# VC8Erework.net
KiCad netlist of a schematic drawn in EAGLE
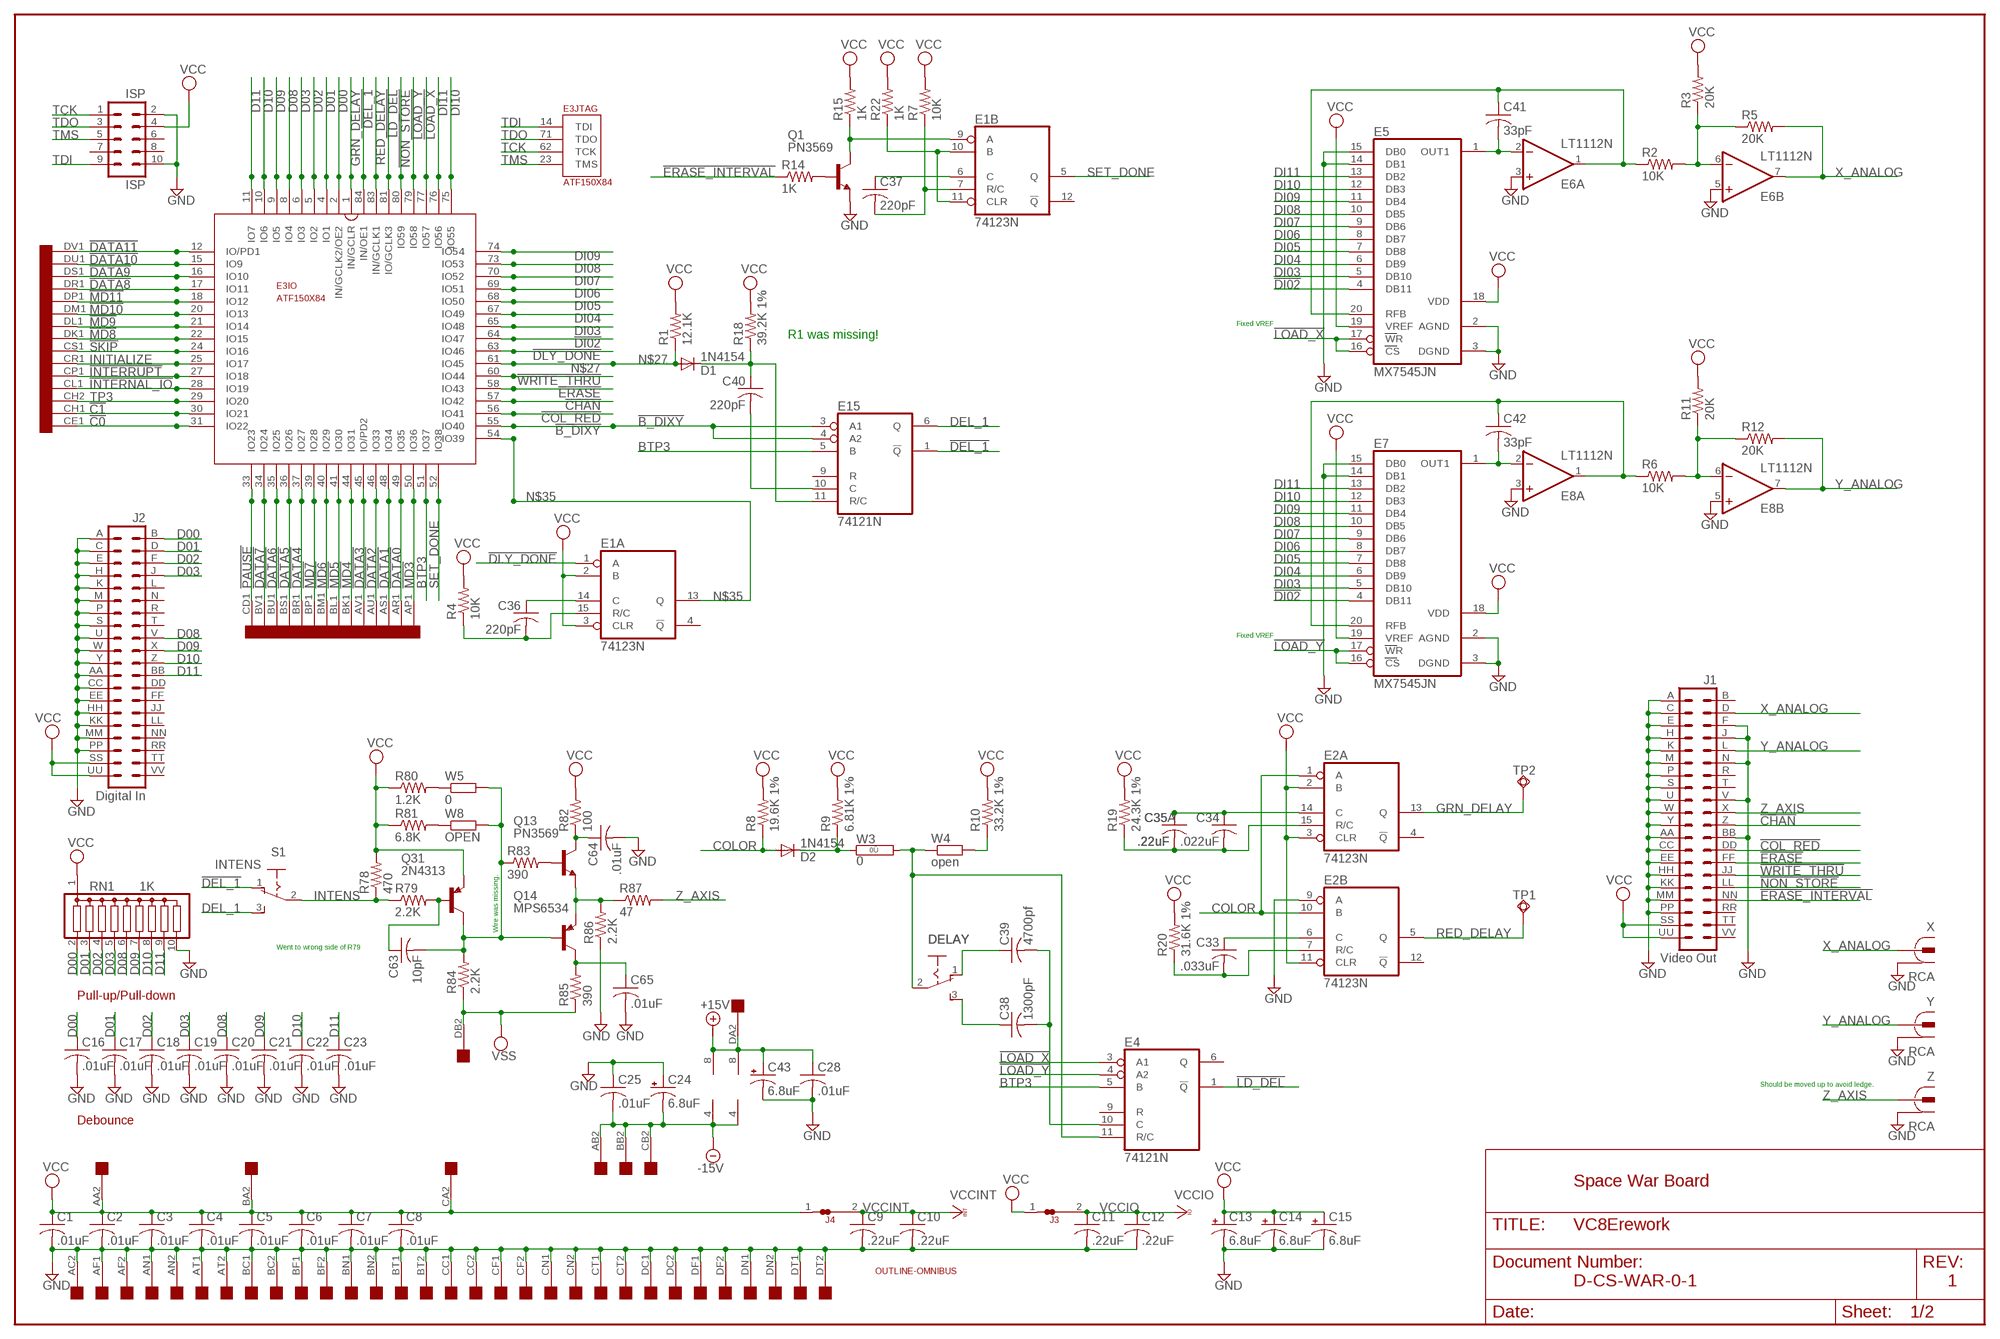
[diagram p0: schematic, sheet 1]

(export (version "E")
  (design (tool "Eeschema 10.0.6"))
  (components
    (comp (ref "C1")
      (value ".01uF")
      (footprint "eagle-import:C063-025X075")
      (libsource (lib "eagle-import") (part "C-US"))
    )
    (comp (ref "C2")
      (value ".01uF")
      (footprint "eagle-import:C063-025X075")
      (libsource (lib "eagle-import") (part "C-US"))
    )
    (comp (ref "C3")
      (value ".01uF")
      (footprint "eagle-import:C063-025X075")
      (libsource (lib "eagle-import") (part "C-US"))
    )
    (comp (ref "C4")
      (value ".01uF")
      (footprint "eagle-import:C063-025X075")
      (libsource (lib "eagle-import") (part "C-US"))
    )
    (comp (ref "C5")
      (value ".01uF")
      (footprint "eagle-import:C063-025X075")
      (libsource (lib "eagle-import") (part "C-US"))
    )
    (comp (ref "C6")
      (value ".01uF")
      (footprint "eagle-import:C063-025X075")
      (libsource (lib "eagle-import") (part "C-US"))
    )
    (comp (ref "C7")
      (value ".01uF")
      (footprint "eagle-import:C063-025X075")
      (libsource (lib "eagle-import") (part "C-US"))
    )
    (comp (ref "C8")
      (value ".01uF")
      (footprint "eagle-import:C063-025X075")
      (libsource (lib "eagle-import") (part "C-US"))
    )
    (comp (ref "C9")
      (value ".22uF")
      (footprint "eagle-import:C063-025X075")
      (libsource (lib "eagle-import") (part "C-US"))
    )
    (comp (ref "C10")
      (value ".22uF")
      (footprint "eagle-import:C063-025X075")
      (libsource (lib "eagle-import") (part "C-US"))
    )
    (comp (ref "C11")
      (value ".22uF")
      (footprint "eagle-import:C063-025X075")
      (libsource (lib "eagle-import") (part "C-US"))
    )
    (comp (ref "C12")
      (value ".22uF")
      (footprint "eagle-import:C063-025X075")
      (libsource (lib "eagle-import") (part "C-US"))
    )
    (comp (ref "C13")
      (value "6.8uF")
      (footprint "eagle-import:E12-8")
      (libsource (lib "eagle-import") (part "CPOL-USE20-8AXIAL"))
    )
    (comp (ref "C14")
      (value "6.8uF")
      (footprint "eagle-import:E12-8")
      (libsource (lib "eagle-import") (part "CPOL-USE20-8AXIAL"))
    )
    (comp (ref "C15")
      (value "6.8uF")
      (footprint "eagle-import:E12-8")
      (libsource (lib "eagle-import") (part "CPOL-USE20-8AXIAL"))
    )
    (comp (ref "C16")
      (value ".01uF")
      (footprint "eagle-import:C063-025X075")
      (libsource (lib "eagle-import") (part "C-US"))
    )
    (comp (ref "C17")
      (value ".01uF")
      (footprint "eagle-import:C063-025X075")
      (libsource (lib "eagle-import") (part "C-US"))
    )
    (comp (ref "C18")
      (value ".01uF")
      (footprint "eagle-import:C063-025X075")
      (libsource (lib "eagle-import") (part "C-US"))
    )
    (comp (ref "C19")
      (value ".01uF")
      (footprint "eagle-import:C063-025X075")
      (libsource (lib "eagle-import") (part "C-US"))
    )
    (comp (ref "C20")
      (value ".01uF")
      (footprint "eagle-import:C063-025X075")
      (libsource (lib "eagle-import") (part "C-US"))
    )
    (comp (ref "C21")
      (value ".01uF")
      (footprint "eagle-import:C063-025X075")
      (libsource (lib "eagle-import") (part "C-US"))
    )
    (comp (ref "C22")
      (value ".01uF")
      (footprint "eagle-import:C063-025X075")
      (libsource (lib "eagle-import") (part "C-US"))
    )
    (comp (ref "C23")
      (value ".01uF")
      (footprint "eagle-import:C063-025X075")
      (libsource (lib "eagle-import") (part "C-US"))
    )
    (comp (ref "C24")
      (value "6.8uF")
      (footprint "eagle-import:E12-8")
      (libsource (lib "eagle-import") (part "CPOL-USE20-8AXIAL"))
    )
    (comp (ref "C25")
      (value ".01uF")
      (footprint "eagle-import:C063-025X075")
      (libsource (lib "eagle-import") (part "C-US"))
    )
    (comp (ref "C28")
      (value ".01uF")
      (footprint "eagle-import:C063-025X075")
      (libsource (lib "eagle-import") (part "C-US"))
    )
    (comp (ref "C33")
      (value ".033uF")
      (footprint "eagle-import:C102-043X133")
      (libsource (lib "eagle-import") (part "C-US102-043X133"))
    )
    (comp (ref "C34")
      (value ".022uF")
      (footprint "eagle-import:C102-043X133")
      (libsource (lib "eagle-import") (part "C-US102-043X133"))
    )
    (comp (ref "C35")
      (value ".22uF")
      (footprint "eagle-import:C050-025X075")
      (libsource (lib "eagle-import") (part "C-US050-025X075"))
    )
    (comp (ref "C35A")
      (value ".22uF")
      (footprint "eagle-import:C102-043X133")
      (libsource (lib "eagle-import") (part "C-US102-043X133"))
    )
    (comp (ref "C36")
      (value "220pF")
      (footprint "eagle-import:C063-025X075")
      (libsource (lib "eagle-import") (part "C-US"))
    )
    (comp (ref "C37")
      (value "220pF")
      (footprint "eagle-import:C063-025X075")
      (libsource (lib "eagle-import") (part "C-US"))
    )
    (comp (ref "C38")
      (value "1300pF")
      (footprint "eagle-import:C150-054X183")
      (libsource (lib "eagle-import") (part "C-US150-054X183"))
    )
    (comp (ref "C39")
      (value "4700pf")
      (footprint "eagle-import:C102-043X133")
      (libsource (lib "eagle-import") (part "C-US102-043X133"))
    )
    (comp (ref "C40")
      (value "220pF")
      (footprint "eagle-import:C063-025X075")
      (libsource (lib "eagle-import") (part "C-US"))
    )
    (comp (ref "C41")
      (value "33pF")
      (footprint "eagle-import:C063-025X075")
      (libsource (lib "eagle-import") (part "C-US"))
    )
    (comp (ref "C42")
      (value "33pF")
      (footprint "eagle-import:C063-025X075")
      (libsource (lib "eagle-import") (part "C-US"))
    )
    (comp (ref "C43")
      (value "6.8uF")
      (footprint "eagle-import:E12-8")
      (libsource (lib "eagle-import") (part "CPOL-USE20-8AXIAL"))
    )
    (comp (ref "C63")
      (value "10pF")
      (footprint "eagle-import:C063-025X075")
      (libsource (lib "eagle-import") (part "C-US"))
    )
    (comp (ref "C64")
      (value ".01uF")
      (footprint "eagle-import:C063-025X075")
      (libsource (lib "eagle-import") (part "C-US"))
    )
    (comp (ref "C65")
      (value ".01uF")
      (footprint "eagle-import:C063-025X075")
      (libsource (lib "eagle-import") (part "C-US"))
    )
    (comp (ref "D1")
      (value "1N4154")
      (footprint "eagle-import:DO35-10")
      (libsource (lib "eagle-import") (part "DIODE-DO35-10"))
    )
    (comp (ref "D2")
      (value "1N4154")
      (footprint "eagle-import:DO35-10")
      (libsource (lib "eagle-import") (part "DIODE-DO35-10"))
    )
    (comp (ref "DELAY")
      (value "DELAY")
      (footprint "eagle-import:M251")
      (libsource (lib "eagle-import") (part "M251"))
    )
    (comp (ref "E1")
      (value "74123N")
      (footprint "eagle-import:DIL16")
      (libsource (lib "eagle-import") (part "74123N"))
    )
    (comp (ref "E2")
      (value "74123N")
      (footprint "eagle-import:DIL16")
      (libsource (lib "eagle-import") (part "74123N"))
    )
    (comp (ref "E3")
      (value "ATF150X84")
      (footprint "eagle-import:S84")
      (libsource (lib "eagle-import") (part "ATF150X84"))
    )
    (comp (ref "E4")
      (value "74121N")
      (footprint "eagle-import:DIL14")
      (libsource (lib "eagle-import") (part "74121N"))
    )
    (comp (ref "E5")
      (value "MX7545JN")
      (footprint "eagle-import:DIL20")
      (fields (field (name "MPN") "MX7545JN+"))
      (libsource (lib "eagle-import") (part "MX7545JN"))
    )
    (comp (ref "E6")
      (value "LT1112N")
      (footprint "eagle-import:DIL08")
      (libsource (lib "eagle-import") (part "1458NLM"))
    )
    (comp (ref "E7")
      (value "MX7545JN")
      (footprint "eagle-import:DIL20")
      (fields (field (name "MPN") "MX7545JN+"))
      (libsource (lib "eagle-import") (part "MX7545JN"))
    )
    (comp (ref "E8")
      (value "LT1112N")
      (footprint "eagle-import:DIL08")
      (libsource (lib "eagle-import") (part "1458NLM"))
    )
    (comp (ref "E15")
      (value "74121N")
      (footprint "eagle-import:DIL14")
      (libsource (lib "eagle-import") (part "74121N"))
    )
    (comp (ref "ISP")
      (value "ISP")
      (footprint "eagle-import:ML10")
      (libsource (lib "eagle-import") (part "ML10"))
    )
    (comp (ref "J1")
      (value "Video Out")
      (footprint "eagle-import:DEC40PINH")
      (libsource (lib "eagle-import") (part "DEC40PINH"))
    )
    (comp (ref "J2")
      (value "Digital In")
      (footprint "eagle-import:DEC40PINH")
      (libsource (lib "eagle-import") (part "DEC40PINH"))
    )
    (comp (ref "J3")
      (value "JUMPER-NC1")
      (footprint "eagle-import:NC1")
      (libsource (lib "eagle-import") (part "JUMPER-NC1"))
    )
    (comp (ref "J4")
      (value "JUMPER-NC1")
      (footprint "eagle-import:NC1")
      (libsource (lib "eagle-import") (part "JUMPER-NC1"))
    )
    (comp (ref "OMNIBUS")
      (value "QUAD")
      (footprint "eagle-import:EDGE-CON8")
      (libsource (lib "eagle-import") (part "QUAD"))
    )
    (comp (ref "Q1")
      (value "PN3569")
      (footprint "eagle-import:TO18-")
      (libsource (lib "eagle-import") (part "-NPN-TO18-"))
    )
    (comp (ref "Q13")
      (value "PN3569")
      (footprint "eagle-import:TO5")
      (libsource (lib "eagle-import") (part "-NPN-TO5"))
    )
    (comp (ref "Q14")
      (value "MPS6534")
      (footprint "eagle-import:TO5")
      (libsource (lib "eagle-import") (part "-PNP-TO5"))
    )
    (comp (ref "Q31")
      (value "2N4313")
      (footprint "eagle-import:TO5")
      (libsource (lib "eagle-import") (part "-PNP-TO5"))
    )
    (comp (ref "R1")
      (value "12.1K")
      (footprint "eagle-import:0207_7")
      (libsource (lib "eagle-import") (part "R-US_0207/7"))
    )
    (comp (ref "R2")
      (value "10K")
      (footprint "eagle-import:0207_10")
      (libsource (lib "eagle-import") (part "R-US_0207/10"))
    )
    (comp (ref "R3")
      (value "20K")
      (footprint "eagle-import:0207_10")
      (libsource (lib "eagle-import") (part "R-US_0207/10"))
    )
    (comp (ref "R4")
      (value "10K")
      (footprint "eagle-import:0207_10")
      (libsource (lib "eagle-import") (part "R-US_0207/10"))
    )
    (comp (ref "R5")
      (value "20K")
      (footprint "eagle-import:0207_10")
      (libsource (lib "eagle-import") (part "R-US_0207/10"))
    )
    (comp (ref "R6")
      (value "10K")
      (footprint "eagle-import:0207_10")
      (libsource (lib "eagle-import") (part "R-US_0207/10"))
    )
    (comp (ref "R7")
      (value "10K")
      (footprint "eagle-import:0207_10")
      (libsource (lib "eagle-import") (part "R-US_0207/10"))
    )
    (comp (ref "R8")
      (value "19.6K 1%")
      (footprint "eagle-import:0207_15")
      (libsource (lib "eagle-import") (part "R-US_0207/15"))
    )
    (comp (ref "R9")
      (value "6.81K 1%")
      (footprint "eagle-import:0207_15")
      (libsource (lib "eagle-import") (part "R-US_0207/15"))
    )
    (comp (ref "R10")
      (value "33.2K 1%")
      (footprint "eagle-import:0207_15")
      (libsource (lib "eagle-import") (part "R-US_0207/15"))
    )
    (comp (ref "R11")
      (value "20K")
      (footprint "eagle-import:0207_10")
      (libsource (lib "eagle-import") (part "R-US_0207/10"))
    )
    (comp (ref "R12")
      (value "20K")
      (footprint "eagle-import:0207_10")
      (libsource (lib "eagle-import") (part "R-US_0207/10"))
    )
    (comp (ref "R14")
      (value "1K")
      (footprint "eagle-import:0207_10")
      (libsource (lib "eagle-import") (part "R-US_0207/10"))
    )
    (comp (ref "R15")
      (value "1K")
      (footprint "eagle-import:0207_10")
      (libsource (lib "eagle-import") (part "R-US_0207/10"))
    )
    (comp (ref "R18")
      (value "39.2K 1%")
      (footprint "eagle-import:0207_15")
      (libsource (lib "eagle-import") (part "R-US_0207/15"))
    )
    (comp (ref "R19")
      (value "24.3K 1%")
      (footprint "eagle-import:0207_15")
      (libsource (lib "eagle-import") (part "R-US_0207/15"))
    )
    (comp (ref "R20")
      (value "31.6K 1%")
      (footprint "eagle-import:0207_15")
      (libsource (lib "eagle-import") (part "R-US_0207/15"))
    )
    (comp (ref "R22")
      (value "1K")
      (footprint "eagle-import:0207_10")
      (libsource (lib "eagle-import") (part "R-US_0207/10"))
    )
    (comp (ref "R78")
      (value "470")
      (footprint "eagle-import:0207_10")
      (libsource (lib "eagle-import") (part "R-US_0207/10"))
    )
    (comp (ref "R79")
      (value "2.2K")
      (footprint "eagle-import:0207_10")
      (libsource (lib "eagle-import") (part "R-US_0207/10"))
    )
    (comp (ref "R80")
      (value "1.2K")
      (footprint "eagle-import:0207_10")
      (libsource (lib "eagle-import") (part "R-US_0207/10"))
    )
    (comp (ref "R81")
      (value "6.8K")
      (footprint "eagle-import:0207_10")
      (libsource (lib "eagle-import") (part "R-US_0207/10"))
    )
    (comp (ref "R82")
      (value "100")
      (footprint "eagle-import:0207_10")
      (libsource (lib "eagle-import") (part "R-US_0207/10"))
    )
    (comp (ref "R83")
      (value "390")
      (footprint "eagle-import:0207_10")
      (libsource (lib "eagle-import") (part "R-US_0207/10"))
    )
    (comp (ref "R84")
      (value "2.2K")
      (footprint "eagle-import:0207_10")
      (libsource (lib "eagle-import") (part "R-US_0207/10"))
    )
    (comp (ref "R85")
      (value "390")
      (footprint "eagle-import:0207_10")
      (libsource (lib "eagle-import") (part "R-US_0207/10"))
    )
    (comp (ref "R86")
      (value "2.2K")
      (footprint "eagle-import:0207_10")
      (libsource (lib "eagle-import") (part "R-US_0207/10"))
    )
    (comp (ref "R87")
      (value "47")
      (footprint "eagle-import:0207_10")
      (libsource (lib "eagle-import") (part "R-US_0207/10"))
    )
    (comp (ref "RN1")
      (value "1K")
      (footprint "eagle-import:SIL10")
      (libsource (lib "eagle-import") (part "G09R"))
    )
    (comp (ref "S1")
      (value "INTENS")
      (footprint "eagle-import:M251")
      (libsource (lib "eagle-import") (part "M251"))
    )
    (comp (ref "TP1")
      (value "TPSQPAD1-17")
      (footprint "eagle-import:P1-17")
      (libsource (lib "eagle-import") (part "TPSQPAD1-17"))
    )
    (comp (ref "TP2")
      (value "TPSQPAD1-17")
      (footprint "eagle-import:P1-17")
      (libsource (lib "eagle-import") (part "TPSQPAD1-17"))
    )
    (comp (ref "U$1")
      (value "OUTLINE-OMNIBUS")
      (footprint "eagle-import:OMNIBUS")
      (libsource (lib "eagle-import") (part "OUTLINE-OMNIBUS"))
    )
    (comp (ref "W3")
      (value "0")
      (footprint "eagle-import:0R_10")
      (libsource (lib "eagle-import") (part "0R"))
    )
    (comp (ref "W4")
      (value "open")
      (footprint "eagle-import:0207_10")
      (libsource (lib "eagle-import") (part "R-EU_0207/10"))
    )
    (comp (ref "W5")
      (value "0")
      (footprint "eagle-import:0207_10")
      (libsource (lib "eagle-import") (part "R-EU_0207/10"))
    )
    (comp (ref "W8")
      (value "OPEN")
      (footprint "eagle-import:0207_10")
      (libsource (lib "eagle-import") (part "R-EU_0207/10"))
    )
    (comp (ref "X")
      (value "RCA")
      (footprint "eagle-import:RCA")
      (libsource (lib "eagle-import") (part "RCA"))
    )
    (comp (ref "Y")
      (value "RCA")
      (footprint "eagle-import:RCA")
      (libsource (lib "eagle-import") (part "RCA"))
    )
    (comp (ref "Z")
      (value "RCA")
      (footprint "eagle-import:RCA")
      (libsource (lib "eagle-import") (part "RCA"))
    )
  )
  (nets
    (net (code "1") (name "+15V") (class "Default")
      (node (ref "C28") (pin "1") (pinfunction "1_1") (pintype "passive"))
      (node (ref "C43") (pin "+") (pinfunction "+_+") (pintype "passive"))
      (node (ref "E6") (pin "8") (pinfunction "V+_8") (pintype "power_in"))
      (node (ref "E8") (pin "8") (pinfunction "V+_8") (pintype "power_in"))
      (node (ref "OMNIBUS") (pin "DA2") (pinfunction "1_DA2") (pintype "bidirectional"))
    )
    (net (code "2") (name "-15V") (class "Default")
      (node (ref "C24") (pin "-") (pinfunction "-_-") (pintype "passive"))
      (node (ref "C25") (pin "2") (pinfunction "2_2") (pintype "passive"))
      (node (ref "E6") (pin "4") (pinfunction "V-_4") (pintype "power_in"))
      (node (ref "E8") (pin "4") (pinfunction "V-_4") (pintype "power_in"))
      (node (ref "OMNIBUS") (pin "AB2") (pinfunction "1_AB2") (pintype "bidirectional"))
      (node (ref "OMNIBUS") (pin "BB2") (pinfunction "1_BB2") (pintype "bidirectional"))
      (node (ref "OMNIBUS") (pin "CB2") (pinfunction "1_CB2") (pintype "bidirectional"))
    )
    (net (code "3") (name "BTP3") (class "Default")
      (node (ref "E15") (pin "5") (pinfunction "B_5") (pintype "input"))
      (node (ref "E3") (pin "51") (pinfunction "IO37_51") (pintype "bidirectional"))
      (node (ref "E4") (pin "5") (pinfunction "B_5") (pintype "input"))
    )
    (net (code "4") (name "COLOR") (class "Default")
      (node (ref "D2") (pin "A") (pinfunction "A_A") (pintype "passive"))
      (node (ref "E2") (pin "1") (pinfunction "A_1") (pintype "input"))
      (node (ref "E2") (pin "10") (pinfunction "B_10") (pintype "input"))
      (node (ref "R8") (pin "1") (pinfunction "1_1") (pintype "passive"))
    )
    (net (code "5") (name "D00") (class "Default")
      (node (ref "C16") (pin "1") (pinfunction "1_1") (pintype "passive"))
      (node (ref "E3") (pin "2") (pinfunction "IN/GCLK2/OE2_2") (pintype "input"))
      (node (ref "J2") (pin "B") (pinfunction "2_B") (pintype "bidirectional"))
      (node (ref "RN1") (pin "2") (pinfunction "2_2") (pintype "passive"))
    )
    (net (code "6") (name "D01") (class "Default")
      (node (ref "C17") (pin "1") (pinfunction "1_1") (pintype "passive"))
      (node (ref "E3") (pin "4") (pinfunction "IO1_4") (pintype "bidirectional"))
      (node (ref "J2") (pin "D") (pinfunction "4_D") (pintype "bidirectional"))
      (node (ref "RN1") (pin "3") (pinfunction "3_3") (pintype "passive"))
    )
    (net (code "7") (name "D02") (class "Default")
      (node (ref "C18") (pin "1") (pinfunction "1_1") (pintype "passive"))
      (node (ref "E3") (pin "5") (pinfunction "IO2_5") (pintype "bidirectional"))
      (node (ref "J2") (pin "F") (pinfunction "6_F") (pintype "bidirectional"))
      (node (ref "RN1") (pin "4") (pinfunction "4_4") (pintype "passive"))
    )
    (net (code "8") (name "D03") (class "Default")
      (node (ref "C19") (pin "1") (pinfunction "1_1") (pintype "passive"))
      (node (ref "E3") (pin "6") (pinfunction "IO3_6") (pintype "bidirectional"))
      (node (ref "J2") (pin "J") (pinfunction "8_J") (pintype "bidirectional"))
      (node (ref "RN1") (pin "5") (pinfunction "5_5") (pintype "passive"))
    )
    (net (code "9") (name "D08") (class "Default")
      (node (ref "C20") (pin "1") (pinfunction "1_1") (pintype "passive"))
      (node (ref "E3") (pin "8") (pinfunction "IO4_8") (pintype "bidirectional"))
      (node (ref "J2") (pin "V") (pinfunction "18_V") (pintype "bidirectional"))
      (node (ref "RN1") (pin "6") (pinfunction "6_6") (pintype "passive"))
    )
    (net (code "10") (name "D09") (class "Default")
      (node (ref "C21") (pin "1") (pinfunction "1_1") (pintype "passive"))
      (node (ref "E3") (pin "9") (pinfunction "IO5_9") (pintype "bidirectional"))
      (node (ref "J2") (pin "X") (pinfunction "20_X") (pintype "bidirectional"))
      (node (ref "RN1") (pin "7") (pinfunction "7_7") (pintype "passive"))
    )
    (net (code "11") (name "D10") (class "Default")
      (node (ref "C22") (pin "1") (pinfunction "1_1") (pintype "passive"))
      (node (ref "E3") (pin "10") (pinfunction "IO6_10") (pintype "bidirectional"))
      (node (ref "J2") (pin "Z") (pinfunction "22_Z") (pintype "bidirectional"))
      (node (ref "RN1") (pin "8") (pinfunction "8_8") (pintype "passive"))
    )
    (net (code "12") (name "D11") (class "Default")
      (node (ref "C23") (pin "1") (pinfunction "1_1") (pintype "passive"))
      (node (ref "E3") (pin "11") (pinfunction "IO7_11") (pintype "bidirectional"))
      (node (ref "J2") (pin "BB") (pinfunction "24_BB") (pintype "bidirectional"))
      (node (ref "RN1") (pin "9") (pinfunction "9_9") (pintype "passive"))
    )
    (net (code "13") (name "DEL_1") (class "Default")
      (node (ref "E15") (pin "6") (pinfunction "Q_6") (pintype "output"))
      (node (ref "S1") (pin "3") (pinfunction "S_3") (pintype "passive"))
    )
    (net (code "14") (name "DI03") (class "Default")
      (node (ref "E3") (pin "65") (pinfunction "IO48_65") (pintype "bidirectional"))
      (node (ref "E5") (pin "5") (pinfunction "DB10_5") (pintype "input"))
      (node (ref "E7") (pin "5") (pinfunction "DB10_5") (pintype "input"))
    )
    (net (code "15") (name "DI04") (class "Default")
      (node (ref "E3") (pin "67") (pinfunction "IO49_67") (pintype "bidirectional"))
      (node (ref "E5") (pin "6") (pinfunction "DB9_6") (pintype "input"))
      (node (ref "E7") (pin "6") (pinfunction "DB9_6") (pintype "input"))
    )
    (net (code "16") (name "DI05") (class "Default")
      (node (ref "E3") (pin "68") (pinfunction "IO50_68") (pintype "bidirectional"))
      (node (ref "E5") (pin "7") (pinfunction "DB8_7") (pintype "input"))
      (node (ref "E7") (pin "7") (pinfunction "DB8_7") (pintype "input"))
    )
    (net (code "17") (name "DI06") (class "Default")
      (node (ref "E3") (pin "69") (pinfunction "IO51_69") (pintype "bidirectional"))
      (node (ref "E5") (pin "8") (pinfunction "DB7_8") (pintype "input"))
      (node (ref "E7") (pin "8") (pinfunction "DB7_8") (pintype "input"))
    )
    (net (code "18") (name "DI07") (class "Default")
      (node (ref "E3") (pin "70") (pinfunction "IO52_70") (pintype "bidirectional"))
      (node (ref "E5") (pin "9") (pinfunction "DB6_9") (pintype "input"))
      (node (ref "E7") (pin "9") (pinfunction "DB6_9") (pintype "input"))
    )
    (net (code "19") (name "DI08") (class "Default")
      (node (ref "E3") (pin "73") (pinfunction "IO53_73") (pintype "bidirectional"))
      (node (ref "E5") (pin "10") (pinfunction "DB5_10") (pintype "input"))
      (node (ref "E7") (pin "10") (pinfunction "DB5_10") (pintype "input"))
    )
    (net (code "20") (name "DI09") (class "Default")
      (node (ref "E3") (pin "74") (pinfunction "IO54_74") (pintype "bidirectional"))
      (node (ref "E5") (pin "11") (pinfunction "DB4_11") (pintype "input"))
      (node (ref "E7") (pin "11") (pinfunction "DB4_11") (pintype "input"))
    )
    (net (code "21") (name "DI10") (class "Default")
      (node (ref "E3") (pin "75") (pinfunction "IO55_75") (pintype "bidirectional"))
      (node (ref "E5") (pin "12") (pinfunction "DB3_12") (pintype "input"))
      (node (ref "E7") (pin "12") (pinfunction "DB3_12") (pintype "input"))
    )
    (net (code "22") (name "DI11") (class "Default")
      (node (ref "E3") (pin "76") (pinfunction "IO56_76") (pintype "bidirectional"))
      (node (ref "E5") (pin "13") (pinfunction "DB2_13") (pintype "input"))
      (node (ref "E7") (pin "13") (pinfunction "DB2_13") (pintype "input"))
    )
    (net (code "23") (name "GND") (class "Default")
      (node (ref "C1") (pin "2") (pinfunction "2_2") (pintype "passive"))
      (node (ref "C10") (pin "2") (pinfunction "2_2") (pintype "passive"))
      (node (ref "C11") (pin "2") (pinfunction "2_2") (pintype "passive"))
      (node (ref "C12") (pin "2") (pinfunction "2_2") (pintype "passive"))
      (node (ref "C13") (pin "-") (pinfunction "-_-") (pintype "passive"))
      (node (ref "C14") (pin "-") (pinfunction "-_-") (pintype "passive"))
      (node (ref "C15") (pin "-") (pinfunction "-_-") (pintype "passive"))
      (node (ref "C16") (pin "2") (pinfunction "2_2") (pintype "passive"))
      (node (ref "C17") (pin "2") (pinfunction "2_2") (pintype "passive"))
      (node (ref "C18") (pin "2") (pinfunction "2_2") (pintype "passive"))
      (node (ref "C19") (pin "2") (pinfunction "2_2") (pintype "passive"))
      (node (ref "C2") (pin "2") (pinfunction "2_2") (pintype "passive"))
      (node (ref "C20") (pin "2") (pinfunction "2_2") (pintype "passive"))
      (node (ref "C21") (pin "2") (pinfunction "2_2") (pintype "passive"))
      (node (ref "C22") (pin "2") (pinfunction "2_2") (pintype "passive"))
      (node (ref "C23") (pin "2") (pinfunction "2_2") (pintype "passive"))
      (node (ref "C24") (pin "+") (pinfunction "+_+") (pintype "passive"))
      (node (ref "C25") (pin "1") (pinfunction "1_1") (pintype "passive"))
      (node (ref "C28") (pin "2") (pinfunction "2_2") (pintype "passive"))
      (node (ref "C3") (pin "2") (pinfunction "2_2") (pintype "passive"))
      (node (ref "C4") (pin "2") (pinfunction "2_2") (pintype "passive"))
      (node (ref "C43") (pin "-") (pinfunction "-_-") (pintype "passive"))
      (node (ref "C5") (pin "2") (pinfunction "2_2") (pintype "passive"))
      (node (ref "C6") (pin "2") (pinfunction "2_2") (pintype "passive"))
      (node (ref "C64") (pin "2") (pinfunction "2_2") (pintype "passive"))
      (node (ref "C65") (pin "2") (pinfunction "2_2") (pintype "passive"))
      (node (ref "C7") (pin "2") (pinfunction "2_2") (pintype "passive"))
      (node (ref "C8") (pin "2") (pinfunction "2_2") (pintype "passive"))
      (node (ref "C9") (pin "2") (pinfunction "2_2") (pintype "passive"))
      (node (ref "E2") (pin "9") (pinfunction "A_9") (pintype "input"))
      (node (ref "E5") (pin "14") (pinfunction "DB1_14") (pintype "input"))
      (node (ref "E5") (pin "15") (pinfunction "DB0_15") (pintype "input"))
      (node (ref "E5") (pin "2") (pinfunction "AGND_2") (pintype "power_in"))
      (node (ref "E5") (pin "3") (pinfunction "DGND_3") (pintype "power_in"))
      (node (ref "E6") (pin "3") (pinfunction "+IN_3") (pintype "input"))
      (node (ref "E6") (pin "5") (pinfunction "+IN_5") (pintype "input"))
      (node (ref "E7") (pin "14") (pinfunction "DB1_14") (pintype "input"))
      (node (ref "E7") (pin "15") (pinfunction "DB0_15") (pintype "input"))
      (node (ref "E7") (pin "2") (pinfunction "AGND_2") (pintype "power_in"))
      (node (ref "E7") (pin "3") (pinfunction "DGND_3") (pintype "power_in"))
      (node (ref "E8") (pin "3") (pinfunction "+IN_3") (pintype "input"))
      (node (ref "E8") (pin "5") (pinfunction "+IN_5") (pintype "input"))
      (node (ref "ISP") (pin "10") (pinfunction "10_10") (pintype "passive"))
      (node (ref "ISP") (pin "2") (pinfunction "2_2") (pintype "passive"))
      (node (ref "J1") (pin "A") (pinfunction "1_A") (pintype "bidirectional"))
      (node (ref "J1") (pin "AA") (pinfunction "23_AA") (pintype "bidirectional"))
      (node (ref "J1") (pin "BB") (pinfunction "24_BB") (pintype "bidirectional"))
      (node (ref "J1") (pin "C") (pinfunction "3_C") (pintype "bidirectional"))
      (node (ref "J1") (pin "CC") (pinfunction "25_CC") (pintype "bidirectional"))
      (node (ref "J1") (pin "E") (pinfunction "5_E") (pintype "bidirectional"))
      (node (ref "J1") (pin "EE") (pinfunction "27_EE") (pintype "bidirectional"))
      (node (ref "J1") (pin "F") (pinfunction "6_F") (pintype "bidirectional"))
      (node (ref "J1") (pin "H") (pinfunction "7_H") (pintype "bidirectional"))
      (node (ref "J1") (pin "HH") (pinfunction "29_HH") (pintype "bidirectional"))
      (node (ref "J1") (pin "J") (pinfunction "8_J") (pintype "bidirectional"))
      (node (ref "J1") (pin "K") (pinfunction "9_K") (pintype "bidirectional"))
      (node (ref "J1") (pin "KK") (pinfunction "31_KK") (pintype "bidirectional"))
      (node (ref "J1") (pin "M") (pinfunction "11_M") (pintype "bidirectional"))
      (node (ref "J1") (pin "MM") (pinfunction "33_MM") (pintype "bidirectional"))
      (node (ref "J1") (pin "N") (pinfunction "12_N") (pintype "bidirectional"))
      (node (ref "J1") (pin "P") (pinfunction "13_P") (pintype "bidirectional"))
      (node (ref "J1") (pin "PP") (pinfunction "35_PP") (pintype "bidirectional"))
      (node (ref "J1") (pin "S") (pinfunction "15_S") (pintype "bidirectional"))
      (node (ref "J1") (pin "U") (pinfunction "17_U") (pintype "bidirectional"))
      (node (ref "J1") (pin "V") (pinfunction "18_V") (pintype "bidirectional"))
      (node (ref "J1") (pin "W") (pinfunction "19_W") (pintype "bidirectional"))
      (node (ref "J1") (pin "Y") (pinfunction "21_Y") (pintype "bidirectional"))
      (node (ref "J2") (pin "A") (pinfunction "1_A") (pintype "bidirectional"))
      (node (ref "J2") (pin "AA") (pinfunction "23_AA") (pintype "bidirectional"))
      (node (ref "J2") (pin "C") (pinfunction "3_C") (pintype "bidirectional"))
      (node (ref "J2") (pin "CC") (pinfunction "25_CC") (pintype "bidirectional"))
      (node (ref "J2") (pin "E") (pinfunction "5_E") (pintype "bidirectional"))
      (node (ref "J2") (pin "EE") (pinfunction "27_EE") (pintype "bidirectional"))
      (node (ref "J2") (pin "H") (pinfunction "7_H") (pintype "bidirectional"))
      (node (ref "J2") (pin "HH") (pinfunction "29_HH") (pintype "bidirectional"))
      (node (ref "J2") (pin "K") (pinfunction "9_K") (pintype "bidirectional"))
      (node (ref "J2") (pin "KK") (pinfunction "31_KK") (pintype "bidirectional"))
      (node (ref "J2") (pin "M") (pinfunction "11_M") (pintype "bidirectional"))
      (node (ref "J2") (pin "MM") (pinfunction "33_MM") (pintype "bidirectional"))
      (node (ref "J2") (pin "P") (pinfunction "13_P") (pintype "bidirectional"))
      (node (ref "J2") (pin "PP") (pinfunction "35_PP") (pintype "bidirectional"))
      (node (ref "J2") (pin "S") (pinfunction "15_S") (pintype "bidirectional"))
      (node (ref "J2") (pin "U") (pinfunction "17_U") (pintype "bidirectional"))
      (node (ref "J2") (pin "W") (pinfunction "19_W") (pintype "bidirectional"))
      (node (ref "J2") (pin "Y") (pinfunction "21_Y") (pintype "bidirectional"))
      (node (ref "OMNIBUS") (pin "AC2") (pinfunction "1_AC2") (pintype "bidirectional"))
      (node (ref "OMNIBUS") (pin "AF1") (pinfunction "1_AF1") (pintype "bidirectional"))
      (node (ref "OMNIBUS") (pin "AF2") (pinfunction "1_AF2") (pintype "bidirectional"))
      (node (ref "OMNIBUS") (pin "AN1") (pinfunction "1_AN1") (pintype "bidirectional"))
      (node (ref "OMNIBUS") (pin "AN2") (pinfunction "1_AN2") (pintype "bidirectional"))
      (node (ref "OMNIBUS") (pin "AT1") (pinfunction "1_AT1") (pintype "bidirectional"))
      (node (ref "OMNIBUS") (pin "AT2") (pinfunction "1_AT2") (pintype "bidirectional"))
      (node (ref "OMNIBUS") (pin "BC1") (pinfunction "1_BC1") (pintype "bidirectional"))
      (node (ref "OMNIBUS") (pin "BC2") (pinfunction "1_BC2") (pintype "bidirectional"))
      (node (ref "OMNIBUS") (pin "BF1") (pinfunction "1_BF1") (pintype "bidirectional"))
      (node (ref "OMNIBUS") (pin "BF2") (pinfunction "1_BF2") (pintype "bidirectional"))
      (node (ref "OMNIBUS") (pin "BN1") (pinfunction "1_BN1") (pintype "bidirectional"))
      (node (ref "OMNIBUS") (pin "BN2") (pinfunction "1_BN2") (pintype "bidirectional"))
      (node (ref "OMNIBUS") (pin "BT1") (pinfunction "1_BT1") (pintype "bidirectional"))
      (node (ref "OMNIBUS") (pin "BT2") (pinfunction "1_BT2") (pintype "bidirectional"))
      (node (ref "OMNIBUS") (pin "CC1") (pinfunction "1_CC1") (pintype "bidirectional"))
      (node (ref "OMNIBUS") (pin "CC2") (pinfunction "1_CC2") (pintype "bidirectional"))
      (node (ref "OMNIBUS") (pin "CF1") (pinfunction "1_CF1") (pintype "bidirectional"))
      (node (ref "OMNIBUS") (pin "CF2") (pinfunction "1_CF2") (pintype "bidirectional"))
      (node (ref "OMNIBUS") (pin "CN1") (pinfunction "1_CN1") (pintype "bidirectional"))
      (node (ref "OMNIBUS") (pin "CN2") (pinfunction "1_CN2") (pintype "bidirectional"))
      (node (ref "OMNIBUS") (pin "CT1") (pinfunction "1_CT1") (pintype "bidirectional"))
      (node (ref "OMNIBUS") (pin "CT2") (pinfunction "1_CT2") (pintype "bidirectional"))
      (node (ref "OMNIBUS") (pin "DC1") (pinfunction "1_DC1") (pintype "bidirectional"))
      (node (ref "OMNIBUS") (pin "DC2") (pinfunction "1_DC2") (pintype "bidirectional"))
      (node (ref "OMNIBUS") (pin "DF1") (pinfunction "1_DF1") (pintype "bidirectional"))
      (node (ref "OMNIBUS") (pin "DF2") (pinfunction "1_DF2") (pintype "bidirectional"))
      (node (ref "OMNIBUS") (pin "DN1") (pinfunction "1_DN1") (pintype "bidirectional"))
      (node (ref "OMNIBUS") (pin "DN2") (pinfunction "1_DN2") (pintype "bidirectional"))
      (node (ref "OMNIBUS") (pin "DT1") (pinfunction "1_DT1") (pintype "bidirectional"))
      (node (ref "OMNIBUS") (pin "DT2") (pinfunction "1_DT2") (pintype "bidirectional"))
      (node (ref "Q1") (pin "1") (pinfunction "E_1") (pintype "passive"))
      (node (ref "R86") (pin "1") (pinfunction "1_1") (pintype "passive"))
      (node (ref "RN1") (pin "10") (pinfunction "10_10") (pintype "passive"))
      (node (ref "X") (pin "1") (pinfunction "1_1") (pintype "passive"))
      (node (ref "X") (pin "1@1") (pinfunction "1_1@1") (pintype "passive"))
      (node (ref "X") (pin "1@2") (pinfunction "1_1@2") (pintype "passive"))
      (node (ref "Y") (pin "1") (pinfunction "1_1") (pintype "passive"))
      (node (ref "Y") (pin "1@1") (pinfunction "1_1@1") (pintype "passive"))
      (node (ref "Y") (pin "1@2") (pinfunction "1_1@2") (pintype "passive"))
      (node (ref "Z") (pin "1") (pinfunction "1_1") (pintype "passive"))
      (node (ref "Z") (pin "1@1") (pinfunction "1_1@1") (pintype "passive"))
      (node (ref "Z") (pin "1@2") (pinfunction "1_1@2") (pintype "passive"))
    )
    (net (code "24") (name "GRN_DELAY") (class "Default")
      (node (ref "E2") (pin "13") (pinfunction "Q_13") (pintype "output"))
      (node (ref "E3") (pin "1") (pinfunction "IN/GCLR_1") (pintype "input"))
      (node (ref "TP2") (pin "TP") (pinfunction "TP_TP") (pintype "input"))
    )
    (net (code "25") (name "INITIALIZE") (class "Default")
      (node (ref "E3") (pin "25") (pinfunction "IO17_25") (pintype "bidirectional"))
      (node (ref "OMNIBUS") (pin "CR1") (pinfunction "1_CR1") (pintype "bidirectional"))
    )
    (net (code "26") (name "INTENS") (class "Default")
      (node (ref "R78") (pin "1") (pinfunction "1_1") (pintype "passive"))
      (node (ref "R79") (pin "1") (pinfunction "1_1") (pintype "passive"))
      (node (ref "S1") (pin "2") (pinfunction "P_2") (pintype "passive"))
    )
    (net (code "27") (name "N$27") (class "Default")
      (node (ref "D1") (pin "A") (pinfunction "A_A") (pintype "passive"))
      (node (ref "E3") (pin "61") (pinfunction "IO45_61") (pintype "bidirectional"))
      (node (ref "R1") (pin "1") (pinfunction "1_1") (pintype "passive"))
    )
    (net (code "28") (name "N$35") (class "Default")
      (node (ref "E1") (pin "13") (pinfunction "Q_13") (pintype "output"))
      (node (ref "E3") (pin "54") (pinfunction "IO39_54") (pintype "bidirectional"))
    )
    (net (code "29") (name "Net-(D2-PadC)") (class "Default")
      (node (ref "D2") (pin "C") (pinfunction "C_C") (pintype "passive"))
      (node (ref "R9") (pin "1") (pinfunction "1_1") (pintype "passive"))
      (node (ref "W3") (pin "1") (pinfunction "1_1") (pintype "passive"))
    )
    (net (code "30") (name "Net-(DELAY-O)") (class "Default")
      (node (ref "C39") (pin "1") (pinfunction "1_1") (pintype "passive"))
      (node (ref "DELAY") (pin "1") (pinfunction "O_1") (pintype "passive"))
    )
    (net (code "31") (name "Net-(DELAY-P)") (class "Default")
      (node (ref "DELAY") (pin "2") (pinfunction "P_2") (pintype "passive"))
      (node (ref "E4") (pin "11") (pinfunction "R/C_11") (pintype "input"))
      (node (ref "W3") (pin "2") (pinfunction "2_2") (pintype "passive"))
      (node (ref "W4") (pin "1") (pinfunction "1_1") (pintype "passive"))
    )
    (net (code "32") (name "Net-(DELAY-S)") (class "Default")
      (node (ref "C38") (pin "1") (pinfunction "1_1") (pintype "passive"))
      (node (ref "DELAY") (pin "3") (pinfunction "S_3") (pintype "passive"))
    )
    (net (code "33") (name "Net-(E1A-C)") (class "Default")
      (node (ref "C36") (pin "1") (pinfunction "1_1") (pintype "passive"))
      (node (ref "E1") (pin "14") (pinfunction "C_14") (pintype "input"))
    )
    (net (code "34") (name "Net-(E1A-R{slash}C)") (class "Default")
      (node (ref "C36") (pin "2") (pinfunction "2_2") (pintype "passive"))
      (node (ref "E1") (pin "15") (pinfunction "R/C_15") (pintype "input"))
      (node (ref "R4") (pin "1") (pinfunction "1_1") (pintype "passive"))
    )
    (net (code "35") (name "Net-(E1B-A)") (class "Default")
      (node (ref "E1") (pin "9") (pinfunction "A_9") (pintype "input"))
      (node (ref "Q1") (pin "3") (pinfunction "C_3") (pintype "passive"))
      (node (ref "R15") (pin "1") (pinfunction "1_1") (pintype "passive"))
    )
    (net (code "36") (name "Net-(E1B-B)") (class "Default")
      (node (ref "E1") (pin "10") (pinfunction "B_10") (pintype "input"))
      (node (ref "E1") (pin "11") (pinfunction "CLR_11") (pintype "input"))
      (node (ref "R22") (pin "1") (pinfunction "1_1") (pintype "passive"))
    )
    (net (code "37") (name "Net-(E1B-C)") (class "Default")
      (node (ref "C37") (pin "1") (pinfunction "1_1") (pintype "passive"))
      (node (ref "E1") (pin "6") (pinfunction "C_6") (pintype "input"))
    )
    (net (code "38") (name "Net-(E1B-R{slash}C)") (class "Default")
      (node (ref "C37") (pin "2") (pinfunction "2_2") (pintype "passive"))
      (node (ref "E1") (pin "7") (pinfunction "R/C_7") (pintype "input"))
      (node (ref "R7") (pin "1") (pinfunction "1_1") (pintype "passive"))
    )
    (net (code "39") (name "Net-(E2A-C)") (class "Default")
      (node (ref "C34") (pin "1") (pinfunction "1_1") (pintype "passive"))
      (node (ref "C35") (pin "1") (pinfunction "1_1") (pintype "passive"))
      (node (ref "C35A") (pin "1") (pinfunction "1_1") (pintype "passive"))
      (node (ref "E2") (pin "14") (pinfunction "C_14") (pintype "input"))
    )
    (net (code "40") (name "Net-(E2A-R{slash}C)") (class "Default")
      (node (ref "C34") (pin "2") (pinfunction "2_2") (pintype "passive"))
      (node (ref "C35") (pin "2") (pinfunction "2_2") (pintype "passive"))
      (node (ref "C35A") (pin "2") (pinfunction "2_2") (pintype "passive"))
      (node (ref "E2") (pin "15") (pinfunction "R/C_15") (pintype "input"))
      (node (ref "R19") (pin "1") (pinfunction "1_1") (pintype "passive"))
    )
    (net (code "41") (name "Net-(E2B-C)") (class "Default")
      (node (ref "C33") (pin "1") (pinfunction "1_1") (pintype "passive"))
      (node (ref "E2") (pin "6") (pinfunction "C_6") (pintype "input"))
    )
    (net (code "42") (name "Net-(E2B-R{slash}C)") (class "Default")
      (node (ref "C33") (pin "2") (pinfunction "2_2") (pintype "passive"))
      (node (ref "E2") (pin "7") (pinfunction "R/C_7") (pintype "input"))
      (node (ref "R20") (pin "1") (pinfunction "1_1") (pintype "passive"))
    )
    (net (code "43") (name "Net-(E4A-C)") (class "Default")
      (node (ref "C38") (pin "2") (pinfunction "2_2") (pintype "passive"))
      (node (ref "C39") (pin "2") (pinfunction "2_2") (pintype "passive"))
      (node (ref "E4") (pin "10") (pinfunction "C_10") (pintype "input"))
    )
    (net (code "44") (name "Net-(E5-OUT1)") (class "Default")
      (node (ref "C41") (pin "2") (pinfunction "2_2") (pintype "passive"))
      (node (ref "E5") (pin "1") (pinfunction "OUT1_1") (pintype "output"))
      (node (ref "E6") (pin "2") (pinfunction "-IN_2") (pintype "input"))
    )
    (net (code "45") (name "Net-(E5-RFB)") (class "Default")
      (node (ref "C41") (pin "1") (pinfunction "1_1") (pintype "passive"))
      (node (ref "E5") (pin "20") (pinfunction "RFB_20") (pintype "input"))
      (node (ref "E6") (pin "1") (pinfunction "OUT_1") (pintype "output"))
      (node (ref "R2") (pin "1") (pinfunction "1_1") (pintype "passive"))
    )
    (net (code "46") (name "Net-(E6B--IN)") (class "Default")
      (node (ref "E6") (pin "6") (pinfunction "-IN_6") (pintype "input"))
      (node (ref "R2") (pin "2") (pinfunction "2_2") (pintype "passive"))
      (node (ref "R3") (pin "1") (pinfunction "1_1") (pintype "passive"))
      (node (ref "R5") (pin "1") (pinfunction "1_1") (pintype "passive"))
    )
    (net (code "47") (name "Net-(E7-OUT1)") (class "Default")
      (node (ref "C42") (pin "2") (pinfunction "2_2") (pintype "passive"))
      (node (ref "E7") (pin "1") (pinfunction "OUT1_1") (pintype "output"))
      (node (ref "E8") (pin "2") (pinfunction "-IN_2") (pintype "input"))
    )
    (net (code "48") (name "Net-(E7-RFB)") (class "Default")
      (node (ref "C42") (pin "1") (pinfunction "1_1") (pintype "passive"))
      (node (ref "E7") (pin "20") (pinfunction "RFB_20") (pintype "input"))
      (node (ref "E8") (pin "1") (pinfunction "OUT_1") (pintype "output"))
      (node (ref "R6") (pin "1") (pinfunction "1_1") (pintype "passive"))
    )
    (net (code "49") (name "Net-(E8B--IN)") (class "Default")
      (node (ref "E8") (pin "6") (pinfunction "-IN_6") (pintype "input"))
      (node (ref "R11") (pin "1") (pinfunction "1_1") (pintype "passive"))
      (node (ref "R12") (pin "1") (pinfunction "1_1") (pintype "passive"))
      (node (ref "R6") (pin "2") (pinfunction "2_2") (pintype "passive"))
    )
    (net (code "50") (name "Net-(E15A-C)") (class "Default")
      (node (ref "C40") (pin "2") (pinfunction "2_2") (pintype "passive"))
      (node (ref "E15") (pin "10") (pinfunction "C_10") (pintype "input"))
    )
    (net (code "51") (name "Net-(E15A-R{slash}C)") (class "Default")
      (node (ref "C40") (pin "1") (pinfunction "1_1") (pintype "passive"))
      (node (ref "D1") (pin "C") (pinfunction "C_C") (pintype "passive"))
      (node (ref "E15") (pin "11") (pinfunction "R/C_11") (pintype "input"))
      (node (ref "R18") (pin "1") (pinfunction "1_1") (pintype "passive"))
    )
    (net (code "52") (name "Net-(Q1-B)") (class "Default")
      (node (ref "Q1") (pin "2") (pinfunction "B_2") (pintype "passive"))
      (node (ref "R14") (pin "2") (pinfunction "2_2") (pintype "passive"))
    )
    (net (code "53") (name "Net-(Q13-B)") (class "Default")
      (node (ref "Q13") (pin "2") (pinfunction "B_2") (pintype "passive"))
      (node (ref "R83") (pin "2") (pinfunction "2_2") (pintype "passive"))
    )
    (net (code "54") (name "Net-(Q13-C)") (class "Default")
      (node (ref "C64") (pin "1") (pinfunction "1_1") (pintype "passive"))
      (node (ref "Q13") (pin "3") (pinfunction "C_3") (pintype "passive"))
      (node (ref "R82") (pin "1") (pinfunction "1_1") (pintype "passive"))
    )
    (net (code "55") (name "Net-(Q13-E)") (class "Default")
      (node (ref "Q13") (pin "1") (pinfunction "E_1") (pintype "passive"))
      (node (ref "Q14") (pin "1") (pinfunction "E_1") (pintype "passive"))
      (node (ref "R86") (pin "2") (pinfunction "2_2") (pintype "passive"))
      (node (ref "R87") (pin "1") (pinfunction "1_1") (pintype "passive"))
    )
    (net (code "56") (name "Net-(Q14-B)") (class "Default")
      (node (ref "C63") (pin "2") (pinfunction "2_2") (pintype "passive"))
      (node (ref "Q14") (pin "2") (pinfunction "B_2") (pintype "passive"))
      (node (ref "Q31") (pin "3") (pinfunction "C_3") (pintype "passive"))
      (node (ref "R83") (pin "1") (pinfunction "1_1") (pintype "passive"))
      (node (ref "R84") (pin "2") (pinfunction "2_2") (pintype "passive"))
      (node (ref "W5") (pin "2") (pinfunction "2_2") (pintype "passive"))
      (node (ref "W8") (pin "2") (pinfunction "2_2") (pintype "passive"))
    )
    (net (code "57") (name "Net-(Q14-C)") (class "Default")
      (node (ref "C65") (pin "1") (pinfunction "1_1") (pintype "passive"))
      (node (ref "Q14") (pin "3") (pinfunction "C_3") (pintype "passive"))
      (node (ref "R85") (pin "2") (pinfunction "2_2") (pintype "passive"))
    )
    (net (code "58") (name "Net-(Q31-B)") (class "Default")
      (node (ref "C63") (pin "1") (pinfunction "1_1") (pintype "passive"))
      (node (ref "Q31") (pin "2") (pinfunction "B_2") (pintype "passive"))
      (node (ref "R79") (pin "2") (pinfunction "2_2") (pintype "passive"))
    )
    (net (code "59") (name "Net-(R10-Pad1)") (class "Default")
      (node (ref "R10") (pin "1") (pinfunction "1_1") (pintype "passive"))
      (node (ref "W4") (pin "2") (pinfunction "2_2") (pintype "passive"))
    )
    (net (code "60") (name "Net-(R80-Pad2)") (class "Default")
      (node (ref "R80") (pin "2") (pinfunction "2_2") (pintype "passive"))
      (node (ref "W5") (pin "1") (pinfunction "1_1") (pintype "passive"))
    )
    (net (code "61") (name "Net-(R81-Pad2)") (class "Default")
      (node (ref "R81") (pin "2") (pinfunction "2_2") (pintype "passive"))
      (node (ref "W8") (pin "1") (pinfunction "1_1") (pintype "passive"))
    )
    (net (code "62") (name "RED_DELAY") (class "Default")
      (node (ref "E2") (pin "5") (pinfunction "Q_5") (pintype "output"))
      (node (ref "E3") (pin "83") (pinfunction "IN/GCLK1_83") (pintype "input"))
      (node (ref "TP1") (pin "TP") (pinfunction "TP_TP") (pintype "input"))
    )
    (net (code "63") (name "SET_DONE") (class "Default")
      (node (ref "E1") (pin "5") (pinfunction "Q_5") (pintype "output"))
      (node (ref "E3") (pin "52") (pinfunction "IO38_52") (pintype "bidirectional"))
    )
    (net (code "64") (name "TCK") (class "Default")
      (node (ref "E3") (pin "62") (pinfunction "TCK_62") (pintype "bidirectional"))
      (node (ref "ISP") (pin "1") (pinfunction "1_1") (pintype "passive"))
    )
    (net (code "65") (name "TDI") (class "Default")
      (node (ref "E3") (pin "14") (pinfunction "TDI_14") (pintype "bidirectional"))
      (node (ref "ISP") (pin "9") (pinfunction "9_9") (pintype "passive"))
    )
    (net (code "66") (name "TDO") (class "Default")
      (node (ref "E3") (pin "71") (pinfunction "TDO_71") (pintype "bidirectional"))
      (node (ref "ISP") (pin "3") (pinfunction "3_3") (pintype "passive"))
    )
    (net (code "67") (name "TMS") (class "Default")
      (node (ref "E3") (pin "23") (pinfunction "TMS_23") (pintype "bidirectional"))
      (node (ref "ISP") (pin "5") (pinfunction "5_5") (pintype "passive"))
    )
    (net (code "68") (name "TP3") (class "Default")
      (node (ref "E3") (pin "29") (pinfunction "IO20_29") (pintype "bidirectional"))
      (node (ref "OMNIBUS") (pin "CH2") (pinfunction "1_CH2") (pintype "bidirectional"))
    )
    (net (code "69") (name "VCC") (class "Default")
      (node (ref "C1") (pin "1") (pinfunction "1_1") (pintype "passive"))
      (node (ref "C13") (pin "+") (pinfunction "+_+") (pintype "passive"))
      (node (ref "C14") (pin "+") (pinfunction "+_+") (pintype "passive"))
      (node (ref "C15") (pin "+") (pinfunction "+_+") (pintype "passive"))
      (node (ref "C2") (pin "1") (pinfunction "1_1") (pintype "passive"))
      (node (ref "C3") (pin "1") (pinfunction "1_1") (pintype "passive"))
      (node (ref "C4") (pin "1") (pinfunction "1_1") (pintype "passive"))
      (node (ref "C5") (pin "1") (pinfunction "1_1") (pintype "passive"))
      (node (ref "C6") (pin "1") (pinfunction "1_1") (pintype "passive"))
      (node (ref "C7") (pin "1") (pinfunction "1_1") (pintype "passive"))
      (node (ref "C8") (pin "1") (pinfunction "1_1") (pintype "passive"))
      (node (ref "E1") (pin "2") (pinfunction "B_2") (pintype "input"))
      (node (ref "E1") (pin "3") (pinfunction "CLR_3") (pintype "input"))
      (node (ref "E2") (pin "11") (pinfunction "CLR_11") (pintype "input"))
      (node (ref "E2") (pin "2") (pinfunction "B_2") (pintype "input"))
      (node (ref "E2") (pin "3") (pinfunction "CLR_3") (pintype "input"))
      (node (ref "E5") (pin "18") (pinfunction "VDD_18") (pintype "power_in"))
      (node (ref "E5") (pin "19") (pinfunction "VREF_19") (pintype "input"))
      (node (ref "E7") (pin "18") (pinfunction "VDD_18") (pintype "power_in"))
      (node (ref "E7") (pin "19") (pinfunction "VREF_19") (pintype "input"))
      (node (ref "ISP") (pin "4") (pinfunction "4_4") (pintype "passive"))
      (node (ref "J1") (pin "SS") (pinfunction "37_SS") (pintype "bidirectional"))
      (node (ref "J1") (pin "UU") (pinfunction "39_UU") (pintype "bidirectional"))
      (node (ref "J2") (pin "SS") (pinfunction "37_SS") (pintype "bidirectional"))
      (node (ref "J2") (pin "UU") (pinfunction "39_UU") (pintype "bidirectional"))
      (node (ref "J3") (pin "1") (pinfunction "1_1") (pintype "bidirectional"))
      (node (ref "J4") (pin "1") (pinfunction "1_1") (pintype "bidirectional"))
      (node (ref "OMNIBUS") (pin "AA2") (pinfunction "1_AA2") (pintype "bidirectional"))
      (node (ref "OMNIBUS") (pin "BA2") (pinfunction "1_BA2") (pintype "bidirectional"))
      (node (ref "OMNIBUS") (pin "CA2") (pinfunction "1_CA2") (pintype "bidirectional"))
      (node (ref "Q31") (pin "1") (pinfunction "E_1") (pintype "passive"))
      (node (ref "R1") (pin "2") (pinfunction "2_2") (pintype "passive"))
      (node (ref "R10") (pin "2") (pinfunction "2_2") (pintype "passive"))
      (node (ref "R11") (pin "2") (pinfunction "2_2") (pintype "passive"))
      (node (ref "R15") (pin "2") (pinfunction "2_2") (pintype "passive"))
      (node (ref "R18") (pin "2") (pinfunction "2_2") (pintype "passive"))
      (node (ref "R19") (pin "2") (pinfunction "2_2") (pintype "passive"))
      (node (ref "R20") (pin "2") (pinfunction "2_2") (pintype "passive"))
      (node (ref "R22") (pin "2") (pinfunction "2_2") (pintype "passive"))
      (node (ref "R3") (pin "2") (pinfunction "2_2") (pintype "passive"))
      (node (ref "R4") (pin "2") (pinfunction "2_2") (pintype "passive"))
      (node (ref "R7") (pin "2") (pinfunction "2_2") (pintype "passive"))
      (node (ref "R78") (pin "2") (pinfunction "2_2") (pintype "passive"))
      (node (ref "R8") (pin "2") (pinfunction "2_2") (pintype "passive"))
      (node (ref "R80") (pin "1") (pinfunction "1_1") (pintype "passive"))
      (node (ref "R81") (pin "1") (pinfunction "1_1") (pintype "passive"))
      (node (ref "R82") (pin "2") (pinfunction "2_2") (pintype "passive"))
      (node (ref "R9") (pin "2") (pinfunction "2_2") (pintype "passive"))
      (node (ref "RN1") (pin "1") (pinfunction "1_1") (pintype "passive"))
    )
    (net (code "70") (name "VCCINT") (class "Default")
      (node (ref "C10") (pin "1") (pinfunction "1_1") (pintype "passive"))
      (node (ref "C9") (pin "1") (pinfunction "1_1") (pintype "passive"))
      (node (ref "J4") (pin "2") (pinfunction "2_2") (pintype "bidirectional"))
    )
    (net (code "71") (name "VCCIO") (class "Default")
      (node (ref "C11") (pin "1") (pinfunction "1_1") (pintype "passive"))
      (node (ref "C12") (pin "1") (pinfunction "1_1") (pintype "passive"))
      (node (ref "J3") (pin "2") (pinfunction "2_2") (pintype "bidirectional"))
    )
    (net (code "72") (name "VSS") (class "Default")
      (node (ref "OMNIBUS") (pin "DB2") (pinfunction "1_DB2") (pintype "bidirectional"))
      (node (ref "R84") (pin "1") (pinfunction "1_1") (pintype "passive"))
      (node (ref "R85") (pin "1") (pinfunction "1_1") (pintype "passive"))
    )
    (net (code "73") (name "X_ANALOG") (class "Default")
      (node (ref "E6") (pin "7") (pinfunction "OUT_7") (pintype "output"))
      (node (ref "J1") (pin "D") (pinfunction "4_D") (pintype "bidirectional"))
      (node (ref "R5") (pin "2") (pinfunction "2_2") (pintype "passive"))
      (node (ref "X") (pin "2") (pinfunction "2_2") (pintype "passive"))
    )
    (net (code "74") (name "Y_ANALOG") (class "Default")
      (node (ref "E8") (pin "7") (pinfunction "OUT_7") (pintype "output"))
      (node (ref "J1") (pin "L") (pinfunction "10_L") (pintype "bidirectional"))
      (node (ref "R12") (pin "2") (pinfunction "2_2") (pintype "passive"))
      (node (ref "Y") (pin "2") (pinfunction "2_2") (pintype "passive"))
    )
    (net (code "75") (name "Z_AXIS") (class "Default")
      (node (ref "J1") (pin "X") (pinfunction "20_X") (pintype "bidirectional"))
      (node (ref "R87") (pin "2") (pinfunction "2_2") (pintype "passive"))
      (node (ref "Z") (pin "2") (pinfunction "2_2") (pintype "passive"))
    )
    (net (code "76") (name "unconnected-(E1A-~{Q}-Pad4)") (class "Default")
      (node (ref "E1") (pin "4") (pinfunction "~{Q}_4") (pintype "output"))
    )
    (net (code "77") (name "unconnected-(E1B-~{Q}-Pad12)") (class "Default")
      (node (ref "E1") (pin "12") (pinfunction "~{Q}_12") (pintype "output"))
    )
    (net (code "78") (name "unconnected-(E2A-~{Q}-Pad4)") (class "Default")
      (node (ref "E2") (pin "4") (pinfunction "~{Q}_4") (pintype "output"))
    )
    (net (code "79") (name "unconnected-(E2B-~{Q}-Pad12)") (class "Default")
      (node (ref "E2") (pin "12") (pinfunction "~{Q}_12") (pintype "output"))
    )
    (net (code "80") (name "unconnected-(E4A-Q-Pad6)") (class "Default")
      (node (ref "E4") (pin "6") (pinfunction "Q_6") (pintype "output"))
    )
    (net (code "81") (name "unconnected-(E4A-R-Pad9)") (class "Default")
      (node (ref "E4") (pin "9") (pinfunction "R_9") (pintype "input"))
    )
    (net (code "82") (name "unconnected-(E15A-R-Pad9)") (class "Default")
      (node (ref "E15") (pin "9") (pinfunction "R_9") (pintype "input"))
    )
    (net (code "83") (name "unconnected-(ISP-Pad6)") (class "Default")
      (node (ref "ISP") (pin "6") (pinfunction "6_6") (pintype "passive"))
    )
    (net (code "84") (name "unconnected-(ISP-Pad7)") (class "Default")
      (node (ref "ISP") (pin "7") (pinfunction "7_7") (pintype "passive"))
    )
    (net (code "85") (name "unconnected-(ISP-Pad8)") (class "Default")
      (node (ref "ISP") (pin "8") (pinfunction "8_8") (pintype "passive"))
    )
    (net (code "86") (name "unconnected-(J1-2-PadB)") (class "Default")
      (node (ref "J1") (pin "B") (pinfunction "2_B") (pintype "bidirectional"))
    )
    (net (code "87") (name "unconnected-(J1-14-PadR)") (class "Default")
      (node (ref "J1") (pin "R") (pinfunction "14_R") (pintype "bidirectional"))
    )
    (net (code "88") (name "unconnected-(J1-16-PadT)") (class "Default")
      (node (ref "J1") (pin "T") (pinfunction "16_T") (pintype "bidirectional"))
    )
    (net (code "89") (name "unconnected-(J1-36-PadRR)") (class "Default")
      (node (ref "J1") (pin "RR") (pinfunction "36_RR") (pintype "bidirectional"))
    )
    (net (code "90") (name "unconnected-(J1-38-PadTT)") (class "Default")
      (node (ref "J1") (pin "TT") (pinfunction "38_TT") (pintype "bidirectional"))
    )
    (net (code "91") (name "unconnected-(J1-40-PadVV)") (class "Default")
      (node (ref "J1") (pin "VV") (pinfunction "40_VV") (pintype "bidirectional"))
    )
    (net (code "92") (name "unconnected-(J2-10-PadL)") (class "Default")
      (node (ref "J2") (pin "L") (pinfunction "10_L") (pintype "bidirectional"))
    )
    (net (code "93") (name "unconnected-(J2-12-PadN)") (class "Default")
      (node (ref "J2") (pin "N") (pinfunction "12_N") (pintype "bidirectional"))
    )
    (net (code "94") (name "unconnected-(J2-14-PadR)") (class "Default")
      (node (ref "J2") (pin "R") (pinfunction "14_R") (pintype "bidirectional"))
    )
    (net (code "95") (name "unconnected-(J2-16-PadT)") (class "Default")
      (node (ref "J2") (pin "T") (pinfunction "16_T") (pintype "bidirectional"))
    )
    (net (code "96") (name "unconnected-(J2-26-PadDD)") (class "Default")
      (node (ref "J2") (pin "DD") (pinfunction "26_DD") (pintype "bidirectional"))
    )
    (net (code "97") (name "unconnected-(J2-28-PadFF)") (class "Default")
      (node (ref "J2") (pin "FF") (pinfunction "28_FF") (pintype "bidirectional"))
    )
    (net (code "98") (name "unconnected-(J2-30-PadJJ)") (class "Default")
      (node (ref "J2") (pin "JJ") (pinfunction "30_JJ") (pintype "bidirectional"))
    )
    (net (code "99") (name "unconnected-(J2-32-PadLL)") (class "Default")
      (node (ref "J2") (pin "LL") (pinfunction "32_LL") (pintype "bidirectional"))
    )
    (net (code "100") (name "unconnected-(J2-34-PadNN)") (class "Default")
      (node (ref "J2") (pin "NN") (pinfunction "34_NN") (pintype "bidirectional"))
    )
    (net (code "101") (name "unconnected-(J2-36-PadRR)") (class "Default")
      (node (ref "J2") (pin "RR") (pinfunction "36_RR") (pintype "bidirectional"))
    )
    (net (code "102") (name "unconnected-(J2-38-PadTT)") (class "Default")
      (node (ref "J2") (pin "TT") (pinfunction "38_TT") (pintype "bidirectional"))
    )
    (net (code "103") (name "unconnected-(J2-40-PadVV)") (class "Default")
      (node (ref "J2") (pin "VV") (pinfunction "40_VV") (pintype "bidirectional"))
    )
    (net (code "104") (name "~{B_DIXY}") (class "Default")
      (node (ref "E15") (pin "3") (pinfunction "A1_3") (pintype "input"))
      (node (ref "E15") (pin "4") (pinfunction "A2_4") (pintype "input"))
      (node (ref "E3") (pin "55") (pinfunction "IO40_55") (pintype "bidirectional"))
    )
    (net (code "105") (name "~{C0}") (class "Default")
      (node (ref "E3") (pin "31") (pinfunction "IO22_31") (pintype "bidirectional"))
      (node (ref "OMNIBUS") (pin "CE1") (pinfunction "1_CE1") (pintype "bidirectional"))
    )
    (net (code "106") (name "~{C1}") (class "Default")
      (node (ref "E3") (pin "30") (pinfunction "IO21_30") (pintype "bidirectional"))
      (node (ref "OMNIBUS") (pin "CH1") (pinfunction "1_CH1") (pintype "bidirectional"))
    )
    (net (code "107") (name "~{CHAN}") (class "Default")
      (node (ref "E3") (pin "57") (pinfunction "IO42_57") (pintype "bidirectional"))
      (node (ref "J1") (pin "Z") (pinfunction "22_Z") (pintype "bidirectional"))
    )
    (net (code "108") (name "~{COL_RED}") (class "Default")
      (node (ref "E3") (pin "56") (pinfunction "IO41_56") (pintype "bidirectional"))
      (node (ref "J1") (pin "DD") (pinfunction "26_DD") (pintype "bidirectional"))
    )
    (net (code "109") (name "~{DATA0}") (class "Default")
      (node (ref "E3") (pin "49") (pinfunction "IO35_49") (pintype "bidirectional"))
      (node (ref "OMNIBUS") (pin "AR1") (pinfunction "1_AR1") (pintype "bidirectional"))
    )
    (net (code "110") (name "~{DATA1}") (class "Default")
      (node (ref "E3") (pin "48") (pinfunction "IO34_48") (pintype "bidirectional"))
      (node (ref "OMNIBUS") (pin "AS1") (pinfunction "1_AS1") (pintype "bidirectional"))
    )
    (net (code "111") (name "~{DATA2}") (class "Default")
      (node (ref "E3") (pin "46") (pinfunction "IO33_46") (pintype "bidirectional"))
      (node (ref "OMNIBUS") (pin "AU1") (pinfunction "1_AU1") (pintype "bidirectional"))
    )
    (net (code "112") (name "~{DATA3}") (class "Default")
      (node (ref "E3") (pin "45") (pinfunction "IO/PD2_45") (pintype "bidirectional"))
      (node (ref "OMNIBUS") (pin "AV1") (pinfunction "1_AV1") (pintype "bidirectional"))
    )
    (net (code "113") (name "~{DATA4}") (class "Default")
      (node (ref "E3") (pin "37") (pinfunction "IO27_37") (pintype "bidirectional"))
      (node (ref "OMNIBUS") (pin "BR1") (pinfunction "1_BR1") (pintype "bidirectional"))
    )
    (net (code "114") (name "~{DATA5}") (class "Default")
      (node (ref "E3") (pin "36") (pinfunction "IO26_36") (pintype "bidirectional"))
      (node (ref "OMNIBUS") (pin "BS1") (pinfunction "1_BS1") (pintype "bidirectional"))
    )
    (net (code "115") (name "~{DATA6}") (class "Default")
      (node (ref "E3") (pin "35") (pinfunction "IO25_35") (pintype "bidirectional"))
      (node (ref "OMNIBUS") (pin "BU1") (pinfunction "1_BU1") (pintype "bidirectional"))
    )
    (net (code "116") (name "~{DATA7}") (class "Default")
      (node (ref "E3") (pin "34") (pinfunction "IO24_34") (pintype "bidirectional"))
      (node (ref "OMNIBUS") (pin "BV1") (pinfunction "1_BV1") (pintype "bidirectional"))
    )
    (net (code "117") (name "~{DATA8}") (class "Default")
      (node (ref "E3") (pin "17") (pinfunction "IO11_17") (pintype "bidirectional"))
      (node (ref "OMNIBUS") (pin "DR1") (pinfunction "1_DR1") (pintype "bidirectional"))
    )
    (net (code "118") (name "~{DATA9}") (class "Default")
      (node (ref "E3") (pin "16") (pinfunction "IO10_16") (pintype "bidirectional"))
      (node (ref "OMNIBUS") (pin "DS1") (pinfunction "1_DS1") (pintype "bidirectional"))
    )
    (net (code "119") (name "~{DATA10}") (class "Default")
      (node (ref "E3") (pin "15") (pinfunction "IO9_15") (pintype "bidirectional"))
      (node (ref "OMNIBUS") (pin "DU1") (pinfunction "1_DU1") (pintype "bidirectional"))
    )
    (net (code "120") (name "~{DATA11}") (class "Default")
      (node (ref "E3") (pin "12") (pinfunction "IO/PD1_12") (pintype "bidirectional"))
      (node (ref "OMNIBUS") (pin "DV1") (pinfunction "1_DV1") (pintype "bidirectional"))
    )
    (net (code "121") (name "~{DEL_1}") (class "Default")
      (node (ref "E15") (pin "1") (pinfunction "~{Q}_1") (pintype "output"))
      (node (ref "E3") (pin "84") (pinfunction "IN/OE1_84") (pintype "input"))
      (node (ref "S1") (pin "1") (pinfunction "O_1") (pintype "passive"))
    )
    (net (code "122") (name "~{DI02}") (class "Default")
      (node (ref "E3") (pin "64") (pinfunction "IO47_64") (pintype "bidirectional"))
      (node (ref "E5") (pin "4") (pinfunction "DB11_4") (pintype "input"))
      (node (ref "E7") (pin "4") (pinfunction "DB11_4") (pintype "input"))
    )
    (net (code "123") (name "~{DLY_DONE}") (class "Default")
      (node (ref "E1") (pin "1") (pinfunction "A_1") (pintype "input"))
      (node (ref "E3") (pin "63") (pinfunction "IO46_63") (pintype "bidirectional"))
    )
    (net (code "124") (name "~{ERASE_INTERVAL}") (class "Default")
      (node (ref "J1") (pin "NN") (pinfunction "34_NN") (pintype "bidirectional"))
      (node (ref "R14") (pin "1") (pinfunction "1_1") (pintype "passive"))
    )
    (net (code "125") (name "~{ERASE}") (class "Default")
      (node (ref "E3") (pin "58") (pinfunction "IO43_58") (pintype "bidirectional"))
      (node (ref "J1") (pin "FF") (pinfunction "28_FF") (pintype "bidirectional"))
    )
    (net (code "126") (name "~{INTERNAL_IO}") (class "Default")
      (node (ref "E3") (pin "28") (pinfunction "IO19_28") (pintype "bidirectional"))
      (node (ref "OMNIBUS") (pin "CL1") (pinfunction "1_CL1") (pintype "bidirectional"))
    )
    (net (code "127") (name "~{INTERRUPT}") (class "Default")
      (node (ref "E3") (pin "27") (pinfunction "IO18_27") (pintype "bidirectional"))
      (node (ref "OMNIBUS") (pin "CP1") (pinfunction "1_CP1") (pintype "bidirectional"))
    )
    (net (code "128") (name "~{LD_DEL}") (class "Default")
      (node (ref "E3") (pin "81") (pinfunction "IO/GCLK3_81") (pintype "bidirectional"))
      (node (ref "E4") (pin "1") (pinfunction "~{Q}_1") (pintype "output"))
    )
    (net (code "129") (name "~{LOAD_X}") (class "Default")
      (node (ref "E3") (pin "77") (pinfunction "IO57_77") (pintype "bidirectional"))
      (node (ref "E4") (pin "3") (pinfunction "A1_3") (pintype "input"))
      (node (ref "E5") (pin "16") (pinfunction "CS_16") (pintype "input"))
      (node (ref "E5") (pin "17") (pinfunction "WR_17") (pintype "input"))
    )
    (net (code "130") (name "~{LOAD_Y}") (class "Default")
      (node (ref "E3") (pin "79") (pinfunction "IO58_79") (pintype "bidirectional"))
      (node (ref "E4") (pin "4") (pinfunction "A2_4") (pintype "input"))
      (node (ref "E7") (pin "16") (pinfunction "CS_16") (pintype "input"))
      (node (ref "E7") (pin "17") (pinfunction "WR_17") (pintype "input"))
    )
    (net (code "131") (name "~{MD3}") (class "Default")
      (node (ref "E3") (pin "50") (pinfunction "IO36_50") (pintype "bidirectional"))
      (node (ref "OMNIBUS") (pin "AP1") (pinfunction "1_AP1") (pintype "bidirectional"))
    )
    (net (code "132") (name "~{MD4}") (class "Default")
      (node (ref "E3") (pin "44") (pinfunction "IO31_44") (pintype "bidirectional"))
      (node (ref "OMNIBUS") (pin "BK1") (pinfunction "1_BK1") (pintype "bidirectional"))
    )
    (net (code "133") (name "~{MD5}") (class "Default")
      (node (ref "E3") (pin "41") (pinfunction "IO30_41") (pintype "bidirectional"))
      (node (ref "OMNIBUS") (pin "BL1") (pinfunction "1_BL1") (pintype "bidirectional"))
    )
    (net (code "134") (name "~{MD6}") (class "Default")
      (node (ref "E3") (pin "40") (pinfunction "IO29_40") (pintype "bidirectional"))
      (node (ref "OMNIBUS") (pin "BM1") (pinfunction "1_BM1") (pintype "bidirectional"))
    )
    (net (code "135") (name "~{MD7}") (class "Default")
      (node (ref "E3") (pin "39") (pinfunction "IO28_39") (pintype "bidirectional"))
      (node (ref "OMNIBUS") (pin "BP1") (pinfunction "1_BP1") (pintype "bidirectional"))
    )
    (net (code "136") (name "~{MD8}") (class "Default")
      (node (ref "E3") (pin "22") (pinfunction "IO15_22") (pintype "bidirectional"))
      (node (ref "OMNIBUS") (pin "DK1") (pinfunction "1_DK1") (pintype "bidirectional"))
    )
    (net (code "137") (name "~{MD9}") (class "Default")
      (node (ref "E3") (pin "21") (pinfunction "IO14_21") (pintype "bidirectional"))
      (node (ref "OMNIBUS") (pin "DL1") (pinfunction "1_DL1") (pintype "bidirectional"))
    )
    (net (code "138") (name "~{MD10}") (class "Default")
      (node (ref "E3") (pin "20") (pinfunction "IO13_20") (pintype "bidirectional"))
      (node (ref "OMNIBUS") (pin "DM1") (pinfunction "1_DM1") (pintype "bidirectional"))
    )
    (net (code "139") (name "~{MD11}") (class "Default")
      (node (ref "E3") (pin "18") (pinfunction "IO12_18") (pintype "bidirectional"))
      (node (ref "OMNIBUS") (pin "DP1") (pinfunction "1_DP1") (pintype "bidirectional"))
    )
    (net (code "140") (name "~{NON_STORE}") (class "Default")
      (node (ref "E3") (pin "80") (pinfunction "IO59_80") (pintype "bidirectional"))
      (node (ref "J1") (pin "LL") (pinfunction "32_LL") (pintype "bidirectional"))
    )
    (net (code "141") (name "~{PAUSE}") (class "Default")
      (node (ref "E3") (pin "33") (pinfunction "IO23_33") (pintype "bidirectional"))
      (node (ref "OMNIBUS") (pin "CD1") (pinfunction "1_CD1") (pintype "bidirectional"))
    )
    (net (code "142") (name "~{SKIP}") (class "Default")
      (node (ref "E3") (pin "24") (pinfunction "IO16_24") (pintype "bidirectional"))
      (node (ref "OMNIBUS") (pin "CS1") (pinfunction "1_CS1") (pintype "bidirectional"))
    )
    (net (code "143") (name "~{WRITE_THRU}") (class "Default")
      (node (ref "E3") (pin "60") (pinfunction "IO44_60") (pintype "bidirectional"))
      (node (ref "J1") (pin "JJ") (pinfunction "30_JJ") (pintype "bidirectional"))
    )
  )
)
